# 007.net
KiCad netlist of a schematic drawn in EAGLE
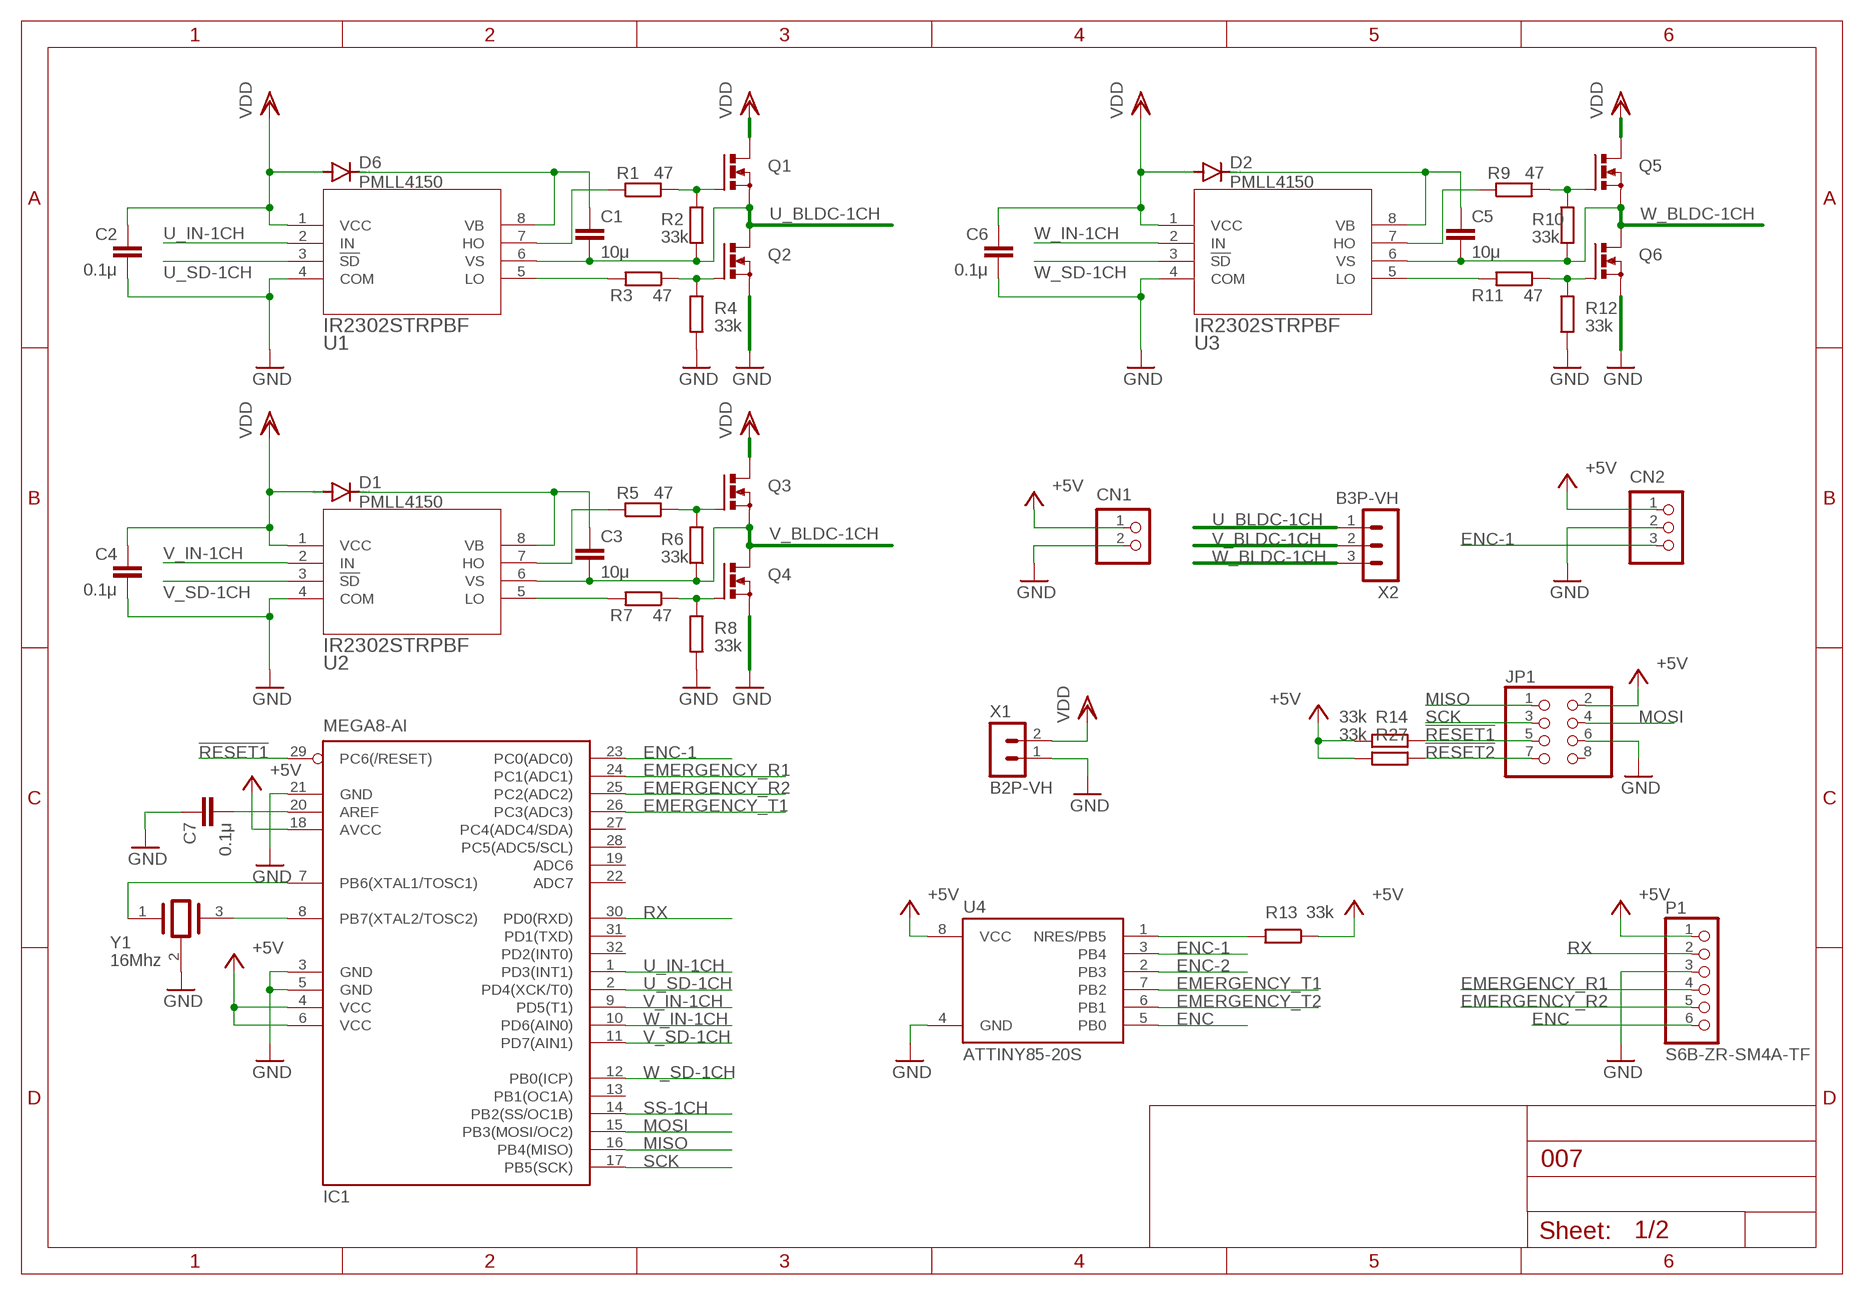
[diagram p0: schematic, sheet 1]
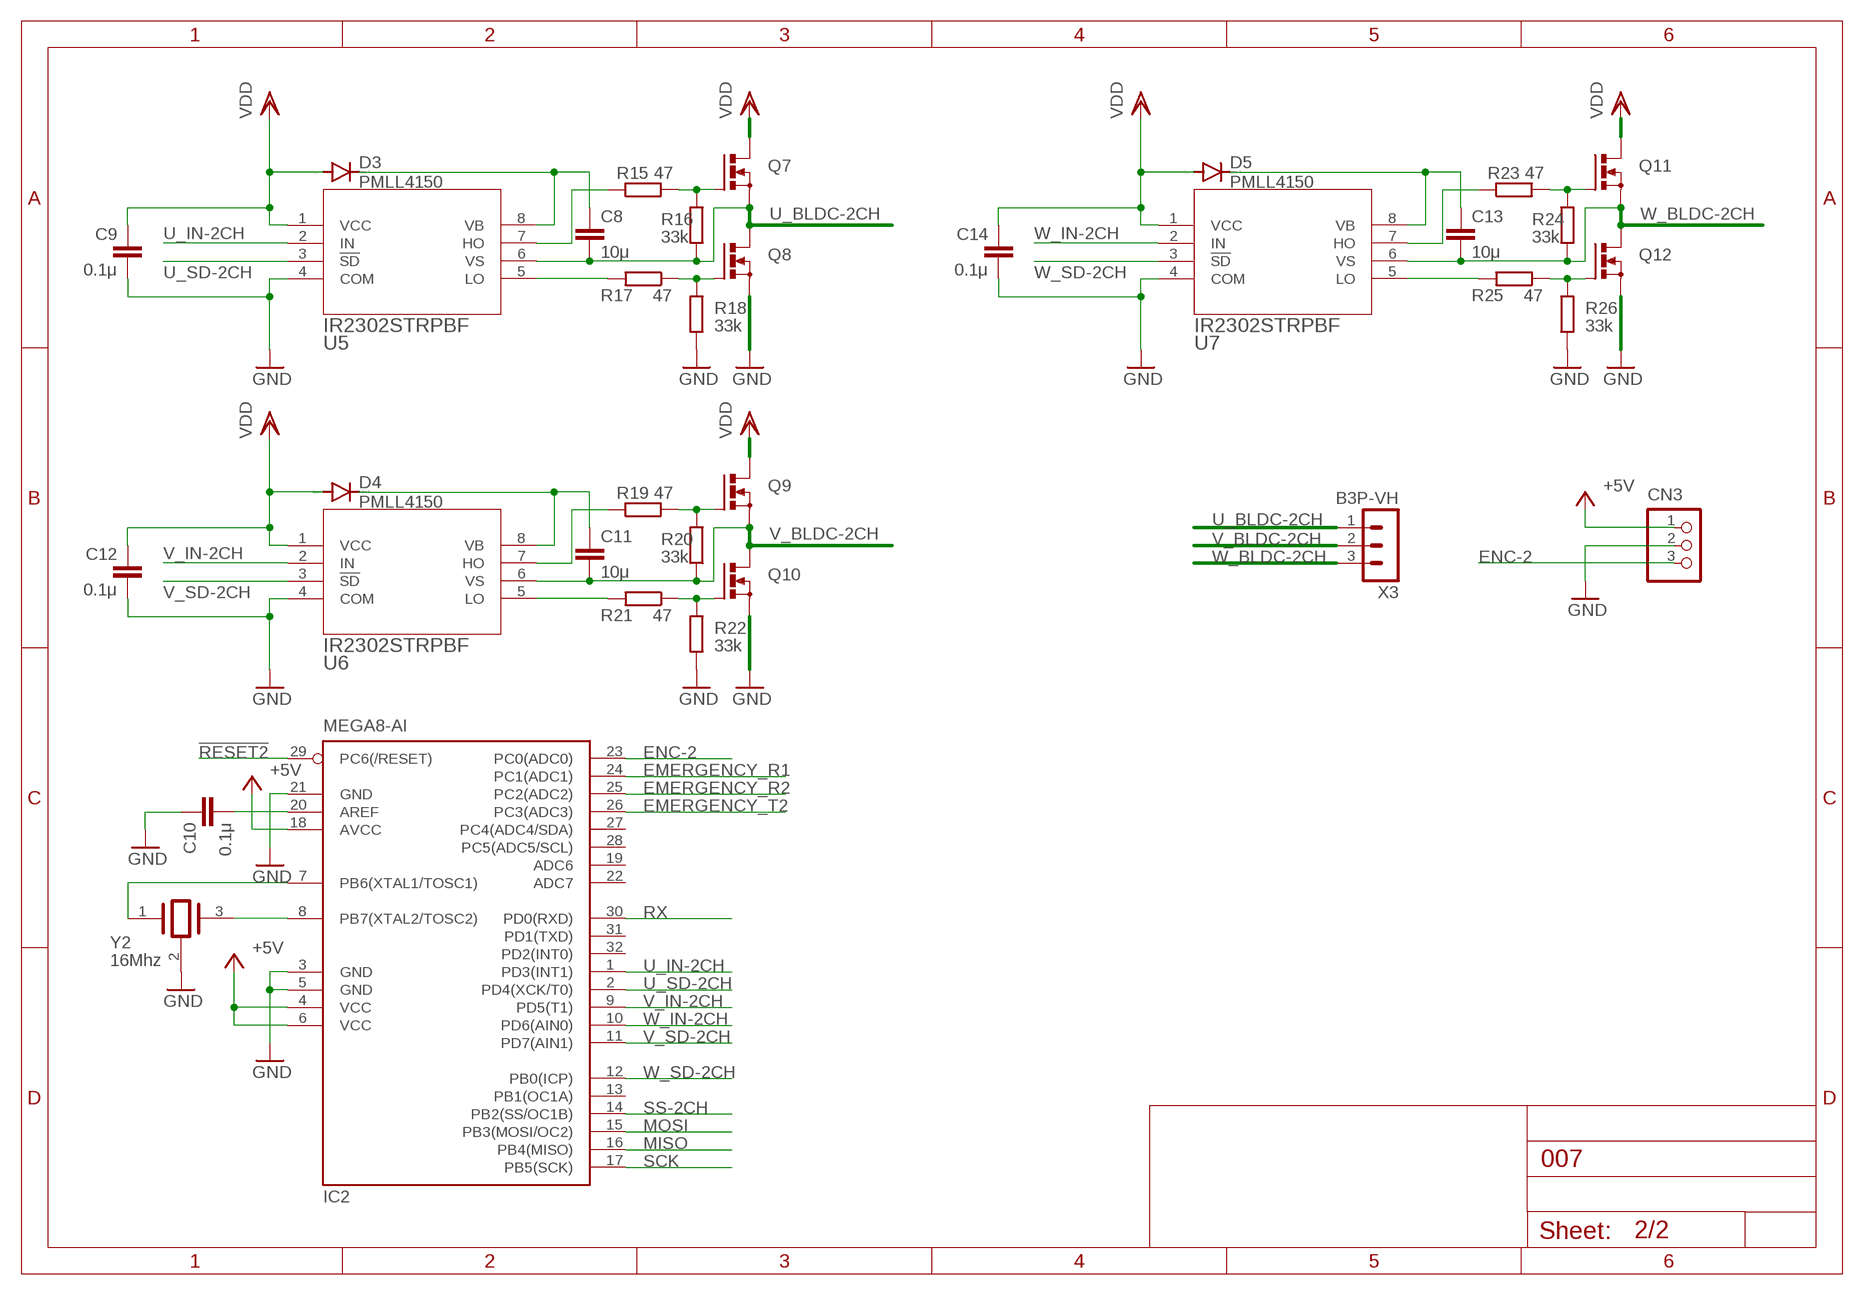
[diagram p1: schematic, sheet 2]

(export (version "E")
  (design (tool "Eeschema 10.0.6"))
  (components
    (comp (ref "C8")
      (value "10μ")
      (footprint "eagle-import:C1608")
      (libsource (lib "eagle-import") (part "C-EUC1608"))
    )
    (comp (ref "C9")
      (value "0.1μ")
      (footprint "eagle-import:C1608")
      (libsource (lib "eagle-import") (part "C-EUC1608"))
    )
    (comp (ref "C10")
      (value "0.1μ")
      (footprint "eagle-import:C1608")
      (libsource (lib "eagle-import") (part "C-EUC1608"))
    )
    (comp (ref "C11")
      (value "10μ")
      (footprint "eagle-import:C1608")
      (libsource (lib "eagle-import") (part "C-EUC1608"))
    )
    (comp (ref "C12")
      (value "0.1μ")
      (footprint "eagle-import:C1608")
      (libsource (lib "eagle-import") (part "C-EUC1608"))
    )
    (comp (ref "C13")
      (value "10μ")
      (footprint "eagle-import:C1608")
      (libsource (lib "eagle-import") (part "C-EUC1608"))
    )
    (comp (ref "C14")
      (value "0.1μ")
      (footprint "eagle-import:C1608")
      (libsource (lib "eagle-import") (part "C-EUC1608"))
    )
    (comp (ref "CN3")
      (value "B3B-PH-K-S")
      (footprint "eagle-import:B3B-PH-K-S")
      (libsource (lib "eagle-import") (part "B3B-PH-K-S"))
    )
    (comp (ref "D3")
      (value "PMLL4150")
      (footprint "eagle-import:SOD80C")
      (libsource (lib "eagle-import") (part "PMLL4150"))
    )
    (comp (ref "D4")
      (value "PMLL4150")
      (footprint "eagle-import:SOD80C")
      (libsource (lib "eagle-import") (part "PMLL4150"))
    )
    (comp (ref "D5")
      (value "PMLL4150")
      (footprint "eagle-import:SOD80C")
      (libsource (lib "eagle-import") (part "PMLL4150"))
    )
    (comp (ref "IC2")
      (value "MEGA8-AI")
      (footprint "eagle-import:TQFP32-08")
      (fields (field (name "MPN") "ATMEGA8-16AU"))
      (libsource (lib "eagle-import") (part "MEGA8-AI"))
    )
    (comp (ref "Q7")
      (value "N-MOSFET-SO8S")
      (footprint "eagle-import:SO-08")
      (libsource (lib "eagle-import") (part "N-MOSFET-SO8S"))
    )
    (comp (ref "Q8")
      (value "N-MOSFET-SO8S")
      (footprint "eagle-import:SO-08")
      (libsource (lib "eagle-import") (part "N-MOSFET-SO8S"))
    )
    (comp (ref "Q9")
      (value "N-MOSFET-SO8S")
      (footprint "eagle-import:SO-08")
      (libsource (lib "eagle-import") (part "N-MOSFET-SO8S"))
    )
    (comp (ref "Q10")
      (value "N-MOSFET-SO8S")
      (footprint "eagle-import:SO-08")
      (libsource (lib "eagle-import") (part "N-MOSFET-SO8S"))
    )
    (comp (ref "Q11")
      (value "N-MOSFET-SO8S")
      (footprint "eagle-import:SO-08")
      (libsource (lib "eagle-import") (part "N-MOSFET-SO8S"))
    )
    (comp (ref "Q12")
      (value "N-MOSFET-SO8S")
      (footprint "eagle-import:SO-08")
      (libsource (lib "eagle-import") (part "N-MOSFET-SO8S"))
    )
    (comp (ref "R15")
      (value "47")
      (footprint "eagle-import:R0603")
      (libsource (lib "eagle-import") (part "R-EU_R0603"))
    )
    (comp (ref "R16")
      (value "33k")
      (footprint "eagle-import:R0603")
      (libsource (lib "eagle-import") (part "R-EU_R0603"))
    )
    (comp (ref "R17")
      (value "47")
      (footprint "eagle-import:R0603")
      (libsource (lib "eagle-import") (part "R-EU_R0603"))
    )
    (comp (ref "R18")
      (value "33k")
      (footprint "eagle-import:R0603")
      (libsource (lib "eagle-import") (part "R-EU_R0603"))
    )
    (comp (ref "R19")
      (value "47")
      (footprint "eagle-import:R0603")
      (libsource (lib "eagle-import") (part "R-EU_R0603"))
    )
    (comp (ref "R20")
      (value "33k")
      (footprint "eagle-import:R0603")
      (libsource (lib "eagle-import") (part "R-EU_R0603"))
    )
    (comp (ref "R21")
      (value "47")
      (footprint "eagle-import:R0603")
      (libsource (lib "eagle-import") (part "R-EU_R0603"))
    )
    (comp (ref "R22")
      (value "33k")
      (footprint "eagle-import:R0603")
      (libsource (lib "eagle-import") (part "R-EU_R0603"))
    )
    (comp (ref "R23")
      (value "47")
      (footprint "eagle-import:R0603")
      (libsource (lib "eagle-import") (part "R-EU_R0603"))
    )
    (comp (ref "R24")
      (value "33k")
      (footprint "eagle-import:R0603")
      (libsource (lib "eagle-import") (part "R-EU_R0603"))
    )
    (comp (ref "R25")
      (value "47")
      (footprint "eagle-import:R0603")
      (libsource (lib "eagle-import") (part "R-EU_R0603"))
    )
    (comp (ref "R26")
      (value "33k")
      (footprint "eagle-import:R0603")
      (libsource (lib "eagle-import") (part "R-EU_R0603"))
    )
    (comp (ref "U5")
      (value "IR2302STRPBF")
      (footprint "eagle-import:PG-DSO-8-910_INF")
      (fields (field (name "COPYRIGHT") "Copyright (C) 2018 Accelerated Designs. All rights reserved"))
      (libsource (lib "eagle-import") (part "IR2302STRPBF"))
    )
    (comp (ref "U6")
      (value "IR2302STRPBF")
      (footprint "eagle-import:PG-DSO-8-910_INF")
      (fields (field (name "COPYRIGHT") "Copyright (C) 2018 Accelerated Designs. All rights reserved"))
      (libsource (lib "eagle-import") (part "IR2302STRPBF"))
    )
    (comp (ref "U7")
      (value "IR2302STRPBF")
      (footprint "eagle-import:PG-DSO-8-910_INF")
      (fields (field (name "COPYRIGHT") "Copyright (C) 2018 Accelerated Designs. All rights reserved"))
      (libsource (lib "eagle-import") (part "IR2302STRPBF"))
    )
    (comp (ref "X3")
      (value "B3P-VH")
      (footprint "eagle-import:B3P-VH")
      (libsource (lib "eagle-import") (part "B3P-VH"))
    )
    (comp (ref "Y2")
      (value "16Mhz")
      (footprint "eagle-import:MURATA_CSTNE16M0V53C000R0_0")
      (fields
        (field (name "DIGIKEY_PART_NUMBER") "490-17949-1-ND")
        (field (name "MF") "Murata")
        (field (name "MOUSER_PART_NUMBER") "81-CSTNE16M0V53C000R")
      )
      (libsource (lib "eagle-import") (part "MURATA_CSTNE16M0V53C000R0MURATA_CSTNE16M0V53C000R0_0_0"))
    )
    (comp (ref "C1")
      (value "10μ")
      (footprint "eagle-import:C1608")
      (libsource (lib "eagle-import") (part "C-EUC1608"))
    )
    (comp (ref "C2")
      (value "0.1μ")
      (footprint "eagle-import:C1608")
      (libsource (lib "eagle-import") (part "C-EUC1608"))
    )
    (comp (ref "C3")
      (value "10μ")
      (footprint "eagle-import:C1608")
      (libsource (lib "eagle-import") (part "C-EUC1608"))
    )
    (comp (ref "C4")
      (value "0.1μ")
      (footprint "eagle-import:C1608")
      (libsource (lib "eagle-import") (part "C-EUC1608"))
    )
    (comp (ref "C5")
      (value "10μ")
      (footprint "eagle-import:C1608")
      (libsource (lib "eagle-import") (part "C-EUC1608"))
    )
    (comp (ref "C6")
      (value "0.1μ")
      (footprint "eagle-import:C1608")
      (libsource (lib "eagle-import") (part "C-EUC1608"))
    )
    (comp (ref "C7")
      (value "0.1μ")
      (footprint "eagle-import:C1608")
      (libsource (lib "eagle-import") (part "C-EUC1608"))
    )
    (comp (ref "CN1")
      (value "B2B-PH-K-S")
      (footprint "eagle-import:B2B-PH-K-S")
      (libsource (lib "eagle-import") (part "B2B-PH-K-S"))
    )
    (comp (ref "CN2")
      (value "B3B-PH-K-S")
      (footprint "eagle-import:B3B-PH-K-S")
      (libsource (lib "eagle-import") (part "B3B-PH-K-S"))
    )
    (comp (ref "D1")
      (value "PMLL4150")
      (footprint "eagle-import:SOD80C")
      (libsource (lib "eagle-import") (part "PMLL4150"))
    )
    (comp (ref "D2")
      (value "PMLL4150")
      (footprint "eagle-import:SOD80C")
      (libsource (lib "eagle-import") (part "PMLL4150"))
    )
    (comp (ref "D6")
      (value "PMLL4150")
      (footprint "eagle-import:SOD80C")
      (libsource (lib "eagle-import") (part "PMLL4150"))
    )
    (comp (ref "IC1")
      (value "MEGA8-AI")
      (footprint "eagle-import:TQFP32-08")
      (fields (field (name "MPN") "ATMEGA8-16AU"))
      (libsource (lib "eagle-import") (part "MEGA8-AI"))
    )
    (comp (ref "JP1")
      (value "PINHD-2X4")
      (footprint "eagle-import:2X04")
      (libsource (lib "eagle-import") (part "PINHD-2X4"))
    )
    (comp (ref "P1")
      (value "S6B-ZR-SM4A-TF")
      (footprint "eagle-import:ZH-SM4-SIDE06")
      (libsource (lib "eagle-import") (part "S6B-ZR-SM4A-TF"))
    )
    (comp (ref "Q1")
      (value "N-MOSFET-SO8S")
      (footprint "eagle-import:SO-08")
      (libsource (lib "eagle-import") (part "N-MOSFET-SO8S"))
    )
    (comp (ref "Q2")
      (value "N-MOSFET-SO8S")
      (footprint "eagle-import:SO-08")
      (libsource (lib "eagle-import") (part "N-MOSFET-SO8S"))
    )
    (comp (ref "Q3")
      (value "N-MOSFET-SO8S")
      (footprint "eagle-import:SO-08")
      (libsource (lib "eagle-import") (part "N-MOSFET-SO8S"))
    )
    (comp (ref "Q4")
      (value "N-MOSFET-SO8S")
      (footprint "eagle-import:SO-08")
      (libsource (lib "eagle-import") (part "N-MOSFET-SO8S"))
    )
    (comp (ref "Q5")
      (value "N-MOSFET-SO8S")
      (footprint "eagle-import:SO-08")
      (libsource (lib "eagle-import") (part "N-MOSFET-SO8S"))
    )
    (comp (ref "Q6")
      (value "N-MOSFET-SO8S")
      (footprint "eagle-import:SO-08")
      (libsource (lib "eagle-import") (part "N-MOSFET-SO8S"))
    )
    (comp (ref "R1")
      (value "47")
      (footprint "eagle-import:R0603")
      (libsource (lib "eagle-import") (part "R-EU_R0603"))
    )
    (comp (ref "R2")
      (value "33k")
      (footprint "eagle-import:R0603")
      (libsource (lib "eagle-import") (part "R-EU_R0603"))
    )
    (comp (ref "R3")
      (value "47")
      (footprint "eagle-import:R0603")
      (libsource (lib "eagle-import") (part "R-EU_R0603"))
    )
    (comp (ref "R4")
      (value "33k")
      (footprint "eagle-import:R0603")
      (libsource (lib "eagle-import") (part "R-EU_R0603"))
    )
    (comp (ref "R5")
      (value "47")
      (footprint "eagle-import:R0603")
      (libsource (lib "eagle-import") (part "R-EU_R0603"))
    )
    (comp (ref "R6")
      (value "33k")
      (footprint "eagle-import:R0603")
      (libsource (lib "eagle-import") (part "R-EU_R0603"))
    )
    (comp (ref "R7")
      (value "47")
      (footprint "eagle-import:R0603")
      (libsource (lib "eagle-import") (part "R-EU_R0603"))
    )
    (comp (ref "R8")
      (value "33k")
      (footprint "eagle-import:R0603")
      (libsource (lib "eagle-import") (part "R-EU_R0603"))
    )
    (comp (ref "R9")
      (value "47")
      (footprint "eagle-import:R0603")
      (libsource (lib "eagle-import") (part "R-EU_R0603"))
    )
    (comp (ref "R10")
      (value "33k")
      (footprint "eagle-import:R0603")
      (libsource (lib "eagle-import") (part "R-EU_R0603"))
    )
    (comp (ref "R11")
      (value "47")
      (footprint "eagle-import:R0603")
      (libsource (lib "eagle-import") (part "R-EU_R0603"))
    )
    (comp (ref "R12")
      (value "33k")
      (footprint "eagle-import:R0603")
      (libsource (lib "eagle-import") (part "R-EU_R0603"))
    )
    (comp (ref "R13")
      (value "33k")
      (footprint "eagle-import:R0603")
      (libsource (lib "eagle-import") (part "R-EU_R0603"))
    )
    (comp (ref "R14")
      (value "33k")
      (footprint "eagle-import:R0603")
      (libsource (lib "eagle-import") (part "R-EU_R0603"))
    )
    (comp (ref "R27")
      (value "33k")
      (footprint "eagle-import:R0603")
      (libsource (lib "eagle-import") (part "R-EU_R0603"))
    )
    (comp (ref "U1")
      (value "IR2302STRPBF")
      (footprint "eagle-import:PG-DSO-8-910_INF")
      (fields (field (name "COPYRIGHT") "Copyright (C) 2018 Accelerated Designs. All rights reserved"))
      (libsource (lib "eagle-import") (part "IR2302STRPBF"))
    )
    (comp (ref "U2")
      (value "IR2302STRPBF")
      (footprint "eagle-import:PG-DSO-8-910_INF")
      (fields (field (name "COPYRIGHT") "Copyright (C) 2018 Accelerated Designs. All rights reserved"))
      (libsource (lib "eagle-import") (part "IR2302STRPBF"))
    )
    (comp (ref "U3")
      (value "IR2302STRPBF")
      (footprint "eagle-import:PG-DSO-8-910_INF")
      (fields (field (name "COPYRIGHT") "Copyright (C) 2018 Accelerated Designs. All rights reserved"))
      (libsource (lib "eagle-import") (part "IR2302STRPBF"))
    )
    (comp (ref "U4")
      (value "ATTINY85-20S")
      (footprint "eagle-import:SOIC8_EIAJ_208MIL")
      (libsource (lib "eagle-import") (part "ATTINY85S-20"))
    )
    (comp (ref "X1")
      (value "B2P-VH")
      (footprint "eagle-import:B2P-VH")
      (libsource (lib "eagle-import") (part "B2P-VH"))
    )
    (comp (ref "X2")
      (value "B3P-VH")
      (footprint "eagle-import:B3P-VH")
      (libsource (lib "eagle-import") (part "B3P-VH"))
    )
    (comp (ref "Y1")
      (value "16Mhz")
      (footprint "eagle-import:MURATA_CSTNE16M0V53C000R0_0")
      (fields
        (field (name "DIGIKEY_PART_NUMBER") "490-17949-1-ND")
        (field (name "MF") "Murata")
        (field (name "MOUSER_PART_NUMBER") "81-CSTNE16M0V53C000R")
      )
      (libsource (lib "eagle-import") (part "MURATA_CSTNE16M0V53C000R0MURATA_CSTNE16M0V53C000R0_0_0"))
    )
  )
  (nets
    (net (code "1") (name "+5V") (class "Default")
      (node (ref "CN1") (pin "1") (pinfunction "1_1") (pintype "passive"))
      (node (ref "CN2") (pin "1") (pinfunction "1_1") (pintype "passive"))
      (node (ref "CN3") (pin "1") (pinfunction "1_1") (pintype "passive"))
      (node (ref "IC1") (pin "18") (pinfunction "AVCC_18") (pintype "power_in"))
      (node (ref "IC1") (pin "4") (pinfunction "VCC_4") (pintype "power_in"))
      (node (ref "IC1") (pin "6") (pinfunction "VCC_6") (pintype "power_in"))
      (node (ref "IC2") (pin "18") (pinfunction "AVCC_18") (pintype "power_in"))
      (node (ref "IC2") (pin "4") (pinfunction "VCC_4") (pintype "power_in"))
      (node (ref "IC2") (pin "6") (pinfunction "VCC_6") (pintype "power_in"))
      (node (ref "JP1") (pin "2") (pinfunction "2_2") (pintype "passive"))
      (node (ref "P1") (pin "1") (pinfunction "1_1") (pintype "passive"))
      (node (ref "R13") (pin "1") (pinfunction "1_1") (pintype "passive"))
      (node (ref "R14") (pin "1") (pinfunction "1_1") (pintype "passive"))
      (node (ref "R27") (pin "1") (pinfunction "1_1") (pintype "passive"))
      (node (ref "U4") (pin "8") (pinfunction "VCC_8") (pintype "power_in"))
    )
    (net (code "2") (name "EMERGENCY_R1") (class "Default")
      (node (ref "IC1") (pin "24") (pinfunction "PC1(ADC1)_24") (pintype "bidirectional"))
      (node (ref "IC2") (pin "24") (pinfunction "PC1(ADC1)_24") (pintype "bidirectional"))
      (node (ref "P1") (pin "4") (pinfunction "4_4") (pintype "passive"))
    )
    (net (code "3") (name "EMERGENCY_R2") (class "Default")
      (node (ref "IC1") (pin "25") (pinfunction "PC2(ADC2)_25") (pintype "bidirectional"))
      (node (ref "IC2") (pin "25") (pinfunction "PC2(ADC2)_25") (pintype "bidirectional"))
      (node (ref "P1") (pin "5") (pinfunction "5_5") (pintype "passive"))
    )
    (net (code "4") (name "EMERGENCY_T1") (class "Default")
      (node (ref "IC1") (pin "26") (pinfunction "PC3(ADC3)_26") (pintype "bidirectional"))
      (node (ref "U4") (pin "7") (pinfunction "PB2_7") (pintype "bidirectional"))
    )
    (net (code "5") (name "EMERGENCY_T2") (class "Default")
      (node (ref "IC2") (pin "26") (pinfunction "PC3(ADC3)_26") (pintype "bidirectional"))
      (node (ref "U4") (pin "6") (pinfunction "PB1_6") (pintype "bidirectional"))
    )
    (net (code "6") (name "ENC") (class "Default")
      (node (ref "P1") (pin "6") (pinfunction "6_6") (pintype "passive"))
      (node (ref "U4") (pin "5") (pinfunction "PB0_5") (pintype "bidirectional"))
    )
    (net (code "7") (name "ENC-1") (class "Default")
      (node (ref "CN2") (pin "3") (pinfunction "3_3") (pintype "passive"))
      (node (ref "IC1") (pin "23") (pinfunction "PC0(ADC0)_23") (pintype "bidirectional"))
      (node (ref "U4") (pin "3") (pinfunction "PB4_3") (pintype "bidirectional"))
    )
    (net (code "8") (name "ENC-2") (class "Default")
      (node (ref "CN3") (pin "3") (pinfunction "3_3") (pintype "passive"))
      (node (ref "IC2") (pin "23") (pinfunction "PC0(ADC0)_23") (pintype "bidirectional"))
      (node (ref "U4") (pin "2") (pinfunction "PB3_2") (pintype "bidirectional"))
    )
    (net (code "9") (name "GND") (class "Default")
      (node (ref "C10") (pin "2") (pinfunction "2_2") (pintype "passive"))
      (node (ref "C12") (pin "1") (pinfunction "1_1") (pintype "passive"))
      (node (ref "C14") (pin "1") (pinfunction "1_1") (pintype "passive"))
      (node (ref "C2") (pin "1") (pinfunction "1_1") (pintype "passive"))
      (node (ref "C4") (pin "1") (pinfunction "1_1") (pintype "passive"))
      (node (ref "C6") (pin "1") (pinfunction "1_1") (pintype "passive"))
      (node (ref "C7") (pin "2") (pinfunction "2_2") (pintype "passive"))
      (node (ref "C9") (pin "1") (pinfunction "1_1") (pintype "passive"))
      (node (ref "CN1") (pin "2") (pinfunction "2_2") (pintype "passive"))
      (node (ref "CN2") (pin "2") (pinfunction "2_2") (pintype "passive"))
      (node (ref "CN3") (pin "2") (pinfunction "2_2") (pintype "passive"))
      (node (ref "IC1") (pin "21") (pinfunction "GND_21") (pintype "power_in"))
      (node (ref "IC1") (pin "3") (pinfunction "GND_3") (pintype "power_in"))
      (node (ref "IC1") (pin "5") (pinfunction "GND_5") (pintype "power_in"))
      (node (ref "IC2") (pin "21") (pinfunction "GND_21") (pintype "power_in"))
      (node (ref "IC2") (pin "3") (pinfunction "GND_3") (pintype "power_in"))
      (node (ref "IC2") (pin "5") (pinfunction "GND_5") (pintype "power_in"))
      (node (ref "JP1") (pin "6") (pinfunction "6_6") (pintype "passive"))
      (node (ref "P1") (pin "3") (pinfunction "3_3") (pintype "passive"))
      (node (ref "Q10") (pin "1") (pinfunction "S_1") (pintype "passive"))
      (node (ref "Q10") (pin "2") (pinfunction "S_2") (pintype "passive"))
      (node (ref "Q10") (pin "3") (pinfunction "S_3") (pintype "passive"))
      (node (ref "Q12") (pin "1") (pinfunction "S_1") (pintype "passive"))
      (node (ref "Q12") (pin "2") (pinfunction "S_2") (pintype "passive"))
      (node (ref "Q12") (pin "3") (pinfunction "S_3") (pintype "passive"))
      (node (ref "Q2") (pin "1") (pinfunction "S_1") (pintype "passive"))
      (node (ref "Q2") (pin "2") (pinfunction "S_2") (pintype "passive"))
      (node (ref "Q2") (pin "3") (pinfunction "S_3") (pintype "passive"))
      (node (ref "Q4") (pin "1") (pinfunction "S_1") (pintype "passive"))
      (node (ref "Q4") (pin "2") (pinfunction "S_2") (pintype "passive"))
      (node (ref "Q4") (pin "3") (pinfunction "S_3") (pintype "passive"))
      (node (ref "Q6") (pin "1") (pinfunction "S_1") (pintype "passive"))
      (node (ref "Q6") (pin "2") (pinfunction "S_2") (pintype "passive"))
      (node (ref "Q6") (pin "3") (pinfunction "S_3") (pintype "passive"))
      (node (ref "Q8") (pin "1") (pinfunction "S_1") (pintype "passive"))
      (node (ref "Q8") (pin "2") (pinfunction "S_2") (pintype "passive"))
      (node (ref "Q8") (pin "3") (pinfunction "S_3") (pintype "passive"))
      (node (ref "R12") (pin "1") (pinfunction "1_1") (pintype "passive"))
      (node (ref "R18") (pin "1") (pinfunction "1_1") (pintype "passive"))
      (node (ref "R22") (pin "1") (pinfunction "1_1") (pintype "passive"))
      (node (ref "R26") (pin "1") (pinfunction "1_1") (pintype "passive"))
      (node (ref "R4") (pin "1") (pinfunction "1_1") (pintype "passive"))
      (node (ref "R8") (pin "1") (pinfunction "1_1") (pintype "passive"))
      (node (ref "U1") (pin "4") (pinfunction "COM_4") (pintype "passive"))
      (node (ref "U2") (pin "4") (pinfunction "COM_4") (pintype "passive"))
      (node (ref "U3") (pin "4") (pinfunction "COM_4") (pintype "passive"))
      (node (ref "U4") (pin "4") (pinfunction "GND_4") (pintype "power_in"))
      (node (ref "U5") (pin "4") (pinfunction "COM_4") (pintype "passive"))
      (node (ref "U6") (pin "4") (pinfunction "COM_4") (pintype "passive"))
      (node (ref "U7") (pin "4") (pinfunction "COM_4") (pintype "passive"))
      (node (ref "X1") (pin "1") (pinfunction "1_1") (pintype "passive"))
      (node (ref "Y1") (pin "2") (pinfunction "GND_2") (pintype "power_in"))
      (node (ref "Y2") (pin "2") (pinfunction "GND_2") (pintype "power_in"))
    )
    (net (code "10") (name "MISO") (class "Default")
      (node (ref "IC1") (pin "16") (pinfunction "PB4(MISO)_16") (pintype "bidirectional"))
      (node (ref "IC2") (pin "16") (pinfunction "PB4(MISO)_16") (pintype "bidirectional"))
      (node (ref "JP1") (pin "1") (pinfunction "1_1") (pintype "passive"))
    )
    (net (code "11") (name "MOSI") (class "Default")
      (node (ref "IC1") (pin "15") (pinfunction "PB3(MOSI/OC2)_15") (pintype "bidirectional"))
      (node (ref "IC2") (pin "15") (pinfunction "PB3(MOSI/OC2)_15") (pintype "bidirectional"))
      (node (ref "JP1") (pin "4") (pinfunction "4_4") (pintype "passive"))
    )
    (net (code "12") (name "Net-(IC1-AREF)") (class "Default")
      (node (ref "C7") (pin "1") (pinfunction "1_1") (pintype "passive"))
      (node (ref "IC1") (pin "20") (pinfunction "AREF_20") (pintype "passive"))
    )
    (net (code "13") (name "Net-(IC1-PB6(XTAL1{slash}TOSC1))") (class "Default")
      (node (ref "IC1") (pin "7") (pinfunction "PB6(XTAL1/TOSC1)_7") (pintype "bidirectional"))
      (node (ref "Y1") (pin "1") (pinfunction "INPUT_1") (pintype "input"))
    )
    (net (code "14") (name "Net-(IC1-PB7(XTAL2{slash}TOSC2))") (class "Default")
      (node (ref "IC1") (pin "8") (pinfunction "PB7(XTAL2/TOSC2)_8") (pintype "bidirectional"))
      (node (ref "Y1") (pin "3") (pinfunction "OUTPUT_3") (pintype "output"))
    )
    (net (code "15") (name "Net-(IC2-AREF)") (class "Default")
      (node (ref "C10") (pin "1") (pinfunction "1_1") (pintype "passive"))
      (node (ref "IC2") (pin "20") (pinfunction "AREF_20") (pintype "passive"))
    )
    (net (code "16") (name "Net-(IC2-PB6(XTAL1{slash}TOSC1))") (class "Default")
      (node (ref "IC2") (pin "7") (pinfunction "PB6(XTAL1/TOSC1)_7") (pintype "bidirectional"))
      (node (ref "Y2") (pin "1") (pinfunction "INPUT_1") (pintype "input"))
    )
    (net (code "17") (name "Net-(IC2-PB7(XTAL2{slash}TOSC2))") (class "Default")
      (node (ref "IC2") (pin "8") (pinfunction "PB7(XTAL2/TOSC2)_8") (pintype "bidirectional"))
      (node (ref "Y2") (pin "3") (pinfunction "OUTPUT_3") (pintype "output"))
    )
    (net (code "18") (name "Net-(Q1-G)") (class "Default")
      (node (ref "Q1") (pin "4") (pinfunction "G_4") (pintype "passive"))
      (node (ref "R1") (pin "2") (pinfunction "2_2") (pintype "passive"))
      (node (ref "R2") (pin "2") (pinfunction "2_2") (pintype "passive"))
    )
    (net (code "19") (name "Net-(Q2-G)") (class "Default")
      (node (ref "Q2") (pin "4") (pinfunction "G_4") (pintype "passive"))
      (node (ref "R3") (pin "1") (pinfunction "1_1") (pintype "passive"))
      (node (ref "R4") (pin "2") (pinfunction "2_2") (pintype "passive"))
    )
    (net (code "20") (name "Net-(Q3-G)") (class "Default")
      (node (ref "Q3") (pin "4") (pinfunction "G_4") (pintype "passive"))
      (node (ref "R5") (pin "2") (pinfunction "2_2") (pintype "passive"))
      (node (ref "R6") (pin "2") (pinfunction "2_2") (pintype "passive"))
    )
    (net (code "21") (name "Net-(Q4-G)") (class "Default")
      (node (ref "Q4") (pin "4") (pinfunction "G_4") (pintype "passive"))
      (node (ref "R7") (pin "1") (pinfunction "1_1") (pintype "passive"))
      (node (ref "R8") (pin "2") (pinfunction "2_2") (pintype "passive"))
    )
    (net (code "22") (name "Net-(Q5-G)") (class "Default")
      (node (ref "Q5") (pin "4") (pinfunction "G_4") (pintype "passive"))
      (node (ref "R10") (pin "2") (pinfunction "2_2") (pintype "passive"))
      (node (ref "R9") (pin "2") (pinfunction "2_2") (pintype "passive"))
    )
    (net (code "23") (name "Net-(Q6-G)") (class "Default")
      (node (ref "Q6") (pin "4") (pinfunction "G_4") (pintype "passive"))
      (node (ref "R11") (pin "1") (pinfunction "1_1") (pintype "passive"))
      (node (ref "R12") (pin "2") (pinfunction "2_2") (pintype "passive"))
    )
    (net (code "24") (name "Net-(Q7-G)") (class "Default")
      (node (ref "Q7") (pin "4") (pinfunction "G_4") (pintype "passive"))
      (node (ref "R15") (pin "2") (pinfunction "2_2") (pintype "passive"))
      (node (ref "R16") (pin "2") (pinfunction "2_2") (pintype "passive"))
    )
    (net (code "25") (name "Net-(Q8-G)") (class "Default")
      (node (ref "Q8") (pin "4") (pinfunction "G_4") (pintype "passive"))
      (node (ref "R17") (pin "1") (pinfunction "1_1") (pintype "passive"))
      (node (ref "R18") (pin "2") (pinfunction "2_2") (pintype "passive"))
    )
    (net (code "26") (name "Net-(Q9-G)") (class "Default")
      (node (ref "Q9") (pin "4") (pinfunction "G_4") (pintype "passive"))
      (node (ref "R19") (pin "2") (pinfunction "2_2") (pintype "passive"))
      (node (ref "R20") (pin "2") (pinfunction "2_2") (pintype "passive"))
    )
    (net (code "27") (name "Net-(Q10-G)") (class "Default")
      (node (ref "Q10") (pin "4") (pinfunction "G_4") (pintype "passive"))
      (node (ref "R21") (pin "1") (pinfunction "1_1") (pintype "passive"))
      (node (ref "R22") (pin "2") (pinfunction "2_2") (pintype "passive"))
    )
    (net (code "28") (name "Net-(Q11-G)") (class "Default")
      (node (ref "Q11") (pin "4") (pinfunction "G_4") (pintype "passive"))
      (node (ref "R23") (pin "2") (pinfunction "2_2") (pintype "passive"))
      (node (ref "R24") (pin "2") (pinfunction "2_2") (pintype "passive"))
    )
    (net (code "29") (name "Net-(Q12-G)") (class "Default")
      (node (ref "Q12") (pin "4") (pinfunction "G_4") (pintype "passive"))
      (node (ref "R25") (pin "1") (pinfunction "1_1") (pintype "passive"))
      (node (ref "R26") (pin "2") (pinfunction "2_2") (pintype "passive"))
    )
    (net (code "30") (name "Net-(U1-HO)") (class "Default")
      (node (ref "R1") (pin "1") (pinfunction "1_1") (pintype "passive"))
      (node (ref "U1") (pin "7") (pinfunction "HO_7") (pintype "output"))
    )
    (net (code "31") (name "Net-(U1-LO)") (class "Default")
      (node (ref "R3") (pin "2") (pinfunction "2_2") (pintype "passive"))
      (node (ref "U1") (pin "5") (pinfunction "LO_5") (pintype "output"))
    )
    (net (code "32") (name "Net-(U1-VB)") (class "Default")
      (node (ref "C1") (pin "1") (pinfunction "1_1") (pintype "passive"))
      (node (ref "D6") (pin "C") (pinfunction "C_C") (pintype "passive"))
      (node (ref "U1") (pin "8") (pinfunction "VB_8") (pintype "power_in"))
    )
    (net (code "33") (name "Net-(U2-HO)") (class "Default")
      (node (ref "R5") (pin "1") (pinfunction "1_1") (pintype "passive"))
      (node (ref "U2") (pin "7") (pinfunction "HO_7") (pintype "output"))
    )
    (net (code "34") (name "Net-(U2-LO)") (class "Default")
      (node (ref "R7") (pin "2") (pinfunction "2_2") (pintype "passive"))
      (node (ref "U2") (pin "5") (pinfunction "LO_5") (pintype "output"))
    )
    (net (code "35") (name "Net-(U2-VB)") (class "Default")
      (node (ref "C3") (pin "1") (pinfunction "1_1") (pintype "passive"))
      (node (ref "D1") (pin "C") (pinfunction "C_C") (pintype "passive"))
      (node (ref "U2") (pin "8") (pinfunction "VB_8") (pintype "power_in"))
    )
    (net (code "36") (name "Net-(U3-HO)") (class "Default")
      (node (ref "R9") (pin "1") (pinfunction "1_1") (pintype "passive"))
      (node (ref "U3") (pin "7") (pinfunction "HO_7") (pintype "output"))
    )
    (net (code "37") (name "Net-(U3-LO)") (class "Default")
      (node (ref "R11") (pin "2") (pinfunction "2_2") (pintype "passive"))
      (node (ref "U3") (pin "5") (pinfunction "LO_5") (pintype "output"))
    )
    (net (code "38") (name "Net-(U3-VB)") (class "Default")
      (node (ref "C5") (pin "1") (pinfunction "1_1") (pintype "passive"))
      (node (ref "D2") (pin "C") (pinfunction "C_C") (pintype "passive"))
      (node (ref "U3") (pin "8") (pinfunction "VB_8") (pintype "power_in"))
    )
    (net (code "39") (name "Net-(U4-NRES{slash}PB5)") (class "Default")
      (node (ref "R13") (pin "2") (pinfunction "2_2") (pintype "passive"))
      (node (ref "U4") (pin "1") (pinfunction "NRES/PB5_1") (pintype "bidirectional"))
    )
    (net (code "40") (name "Net-(U5-HO)") (class "Default")
      (node (ref "R15") (pin "1") (pinfunction "1_1") (pintype "passive"))
      (node (ref "U5") (pin "7") (pinfunction "HO_7") (pintype "output"))
    )
    (net (code "41") (name "Net-(U5-LO)") (class "Default")
      (node (ref "R17") (pin "2") (pinfunction "2_2") (pintype "passive"))
      (node (ref "U5") (pin "5") (pinfunction "LO_5") (pintype "output"))
    )
    (net (code "42") (name "Net-(U5-VB)") (class "Default")
      (node (ref "C8") (pin "1") (pinfunction "1_1") (pintype "passive"))
      (node (ref "D3") (pin "C") (pinfunction "C_C") (pintype "passive"))
      (node (ref "U5") (pin "8") (pinfunction "VB_8") (pintype "power_in"))
    )
    (net (code "43") (name "Net-(U6-HO)") (class "Default")
      (node (ref "R19") (pin "1") (pinfunction "1_1") (pintype "passive"))
      (node (ref "U6") (pin "7") (pinfunction "HO_7") (pintype "output"))
    )
    (net (code "44") (name "Net-(U6-LO)") (class "Default")
      (node (ref "R21") (pin "2") (pinfunction "2_2") (pintype "passive"))
      (node (ref "U6") (pin "5") (pinfunction "LO_5") (pintype "output"))
    )
    (net (code "45") (name "Net-(U6-VB)") (class "Default")
      (node (ref "C11") (pin "1") (pinfunction "1_1") (pintype "passive"))
      (node (ref "D4") (pin "C") (pinfunction "C_C") (pintype "passive"))
      (node (ref "U6") (pin "8") (pinfunction "VB_8") (pintype "power_in"))
    )
    (net (code "46") (name "Net-(U7-HO)") (class "Default")
      (node (ref "R23") (pin "1") (pinfunction "1_1") (pintype "passive"))
      (node (ref "U7") (pin "7") (pinfunction "HO_7") (pintype "output"))
    )
    (net (code "47") (name "Net-(U7-LO)") (class "Default")
      (node (ref "R25") (pin "2") (pinfunction "2_2") (pintype "passive"))
      (node (ref "U7") (pin "5") (pinfunction "LO_5") (pintype "output"))
    )
    (net (code "48") (name "Net-(U7-VB)") (class "Default")
      (node (ref "C13") (pin "1") (pinfunction "1_1") (pintype "passive"))
      (node (ref "D5") (pin "C") (pinfunction "C_C") (pintype "passive"))
      (node (ref "U7") (pin "8") (pinfunction "VB_8") (pintype "power_in"))
    )
    (net (code "49") (name "RX") (class "Default")
      (node (ref "IC1") (pin "30") (pinfunction "PD0(RXD)_30") (pintype "bidirectional"))
      (node (ref "IC2") (pin "30") (pinfunction "PD0(RXD)_30") (pintype "bidirectional"))
      (node (ref "P1") (pin "2") (pinfunction "2_2") (pintype "passive"))
    )
    (net (code "50") (name "SCK") (class "Default")
      (node (ref "IC1") (pin "17") (pinfunction "PB5(SCK)_17") (pintype "bidirectional"))
      (node (ref "IC2") (pin "17") (pinfunction "PB5(SCK)_17") (pintype "bidirectional"))
      (node (ref "JP1") (pin "3") (pinfunction "3_3") (pintype "passive"))
    )
    (net (code "51") (name "SS-1CH") (class "Default")
      (node (ref "IC1") (pin "14") (pinfunction "PB2(SS/OC1B)_14") (pintype "bidirectional"))
    )
    (net (code "52") (name "SS-2CH") (class "Default")
      (node (ref "IC2") (pin "14") (pinfunction "PB2(SS/OC1B)_14") (pintype "bidirectional"))
    )
    (net (code "53") (name "U_BLDC-1CH") (class "Default")
      (node (ref "C1") (pin "2") (pinfunction "2_2") (pintype "passive"))
      (node (ref "Q1") (pin "1") (pinfunction "S_1") (pintype "passive"))
      (node (ref "Q1") (pin "2") (pinfunction "S_2") (pintype "passive"))
      (node (ref "Q1") (pin "3") (pinfunction "S_3") (pintype "passive"))
      (node (ref "Q2") (pin "5") (pinfunction "D_5") (pintype "passive"))
      (node (ref "Q2") (pin "6") (pinfunction "D_6") (pintype "passive"))
      (node (ref "Q2") (pin "7") (pinfunction "D_7") (pintype "passive"))
      (node (ref "Q2") (pin "8") (pinfunction "D_8") (pintype "passive"))
      (node (ref "R2") (pin "1") (pinfunction "1_1") (pintype "passive"))
      (node (ref "U1") (pin "6") (pinfunction "VS_6") (pintype "power_in"))
      (node (ref "X2") (pin "1") (pinfunction "1_1") (pintype "passive"))
    )
    (net (code "54") (name "U_BLDC-2CH") (class "Default")
      (node (ref "C8") (pin "2") (pinfunction "2_2") (pintype "passive"))
      (node (ref "Q7") (pin "1") (pinfunction "S_1") (pintype "passive"))
      (node (ref "Q7") (pin "2") (pinfunction "S_2") (pintype "passive"))
      (node (ref "Q7") (pin "3") (pinfunction "S_3") (pintype "passive"))
      (node (ref "Q8") (pin "5") (pinfunction "D_5") (pintype "passive"))
      (node (ref "Q8") (pin "6") (pinfunction "D_6") (pintype "passive"))
      (node (ref "Q8") (pin "7") (pinfunction "D_7") (pintype "passive"))
      (node (ref "Q8") (pin "8") (pinfunction "D_8") (pintype "passive"))
      (node (ref "R16") (pin "1") (pinfunction "1_1") (pintype "passive"))
      (node (ref "U5") (pin "6") (pinfunction "VS_6") (pintype "power_in"))
      (node (ref "X3") (pin "1") (pinfunction "1_1") (pintype "passive"))
    )
    (net (code "55") (name "U_IN-1CH") (class "Default")
      (node (ref "IC1") (pin "1") (pinfunction "PD3(INT1)_1") (pintype "bidirectional"))
      (node (ref "U1") (pin "2") (pinfunction "IN_2") (pintype "input"))
    )
    (net (code "56") (name "U_IN-2CH") (class "Default")
      (node (ref "IC2") (pin "1") (pinfunction "PD3(INT1)_1") (pintype "bidirectional"))
      (node (ref "U5") (pin "2") (pinfunction "IN_2") (pintype "input"))
    )
    (net (code "57") (name "U_SD-1CH") (class "Default")
      (node (ref "IC1") (pin "2") (pinfunction "PD4(XCK/T0)_2") (pintype "bidirectional"))
      (node (ref "U1") (pin "3") (pinfunction "~{SD}_3") (pintype "input"))
    )
    (net (code "58") (name "U_SD-2CH") (class "Default")
      (node (ref "IC2") (pin "2") (pinfunction "PD4(XCK/T0)_2") (pintype "bidirectional"))
      (node (ref "U5") (pin "3") (pinfunction "~{SD}_3") (pintype "input"))
    )
    (net (code "59") (name "VDD") (class "Default")
      (node (ref "C12") (pin "2") (pinfunction "2_2") (pintype "passive"))
      (node (ref "C14") (pin "2") (pinfunction "2_2") (pintype "passive"))
      (node (ref "C2") (pin "2") (pinfunction "2_2") (pintype "passive"))
      (node (ref "C4") (pin "2") (pinfunction "2_2") (pintype "passive"))
      (node (ref "C6") (pin "2") (pinfunction "2_2") (pintype "passive"))
      (node (ref "C9") (pin "2") (pinfunction "2_2") (pintype "passive"))
      (node (ref "D1") (pin "A") (pinfunction "A_A") (pintype "passive"))
      (node (ref "D2") (pin "A") (pinfunction "A_A") (pintype "passive"))
      (node (ref "D3") (pin "A") (pinfunction "A_A") (pintype "passive"))
      (node (ref "D4") (pin "A") (pinfunction "A_A") (pintype "passive"))
      (node (ref "D5") (pin "A") (pinfunction "A_A") (pintype "passive"))
      (node (ref "D6") (pin "A") (pinfunction "A_A") (pintype "passive"))
      (node (ref "Q1") (pin "5") (pinfunction "D_5") (pintype "passive"))
      (node (ref "Q1") (pin "6") (pinfunction "D_6") (pintype "passive"))
      (node (ref "Q1") (pin "7") (pinfunction "D_7") (pintype "passive"))
      (node (ref "Q1") (pin "8") (pinfunction "D_8") (pintype "passive"))
      (node (ref "Q11") (pin "5") (pinfunction "D_5") (pintype "passive"))
      (node (ref "Q11") (pin "6") (pinfunction "D_6") (pintype "passive"))
      (node (ref "Q11") (pin "7") (pinfunction "D_7") (pintype "passive"))
      (node (ref "Q11") (pin "8") (pinfunction "D_8") (pintype "passive"))
      (node (ref "Q3") (pin "5") (pinfunction "D_5") (pintype "passive"))
      (node (ref "Q3") (pin "6") (pinfunction "D_6") (pintype "passive"))
      (node (ref "Q3") (pin "7") (pinfunction "D_7") (pintype "passive"))
      (node (ref "Q3") (pin "8") (pinfunction "D_8") (pintype "passive"))
      (node (ref "Q5") (pin "5") (pinfunction "D_5") (pintype "passive"))
      (node (ref "Q5") (pin "6") (pinfunction "D_6") (pintype "passive"))
      (node (ref "Q5") (pin "7") (pinfunction "D_7") (pintype "passive"))
      (node (ref "Q5") (pin "8") (pinfunction "D_8") (pintype "passive"))
      (node (ref "Q7") (pin "5") (pinfunction "D_5") (pintype "passive"))
      (node (ref "Q7") (pin "6") (pinfunction "D_6") (pintype "passive"))
      (node (ref "Q7") (pin "7") (pinfunction "D_7") (pintype "passive"))
      (node (ref "Q7") (pin "8") (pinfunction "D_8") (pintype "passive"))
      (node (ref "Q9") (pin "5") (pinfunction "D_5") (pintype "passive"))
      (node (ref "Q9") (pin "6") (pinfunction "D_6") (pintype "passive"))
      (node (ref "Q9") (pin "7") (pinfunction "D_7") (pintype "passive"))
      (node (ref "Q9") (pin "8") (pinfunction "D_8") (pintype "passive"))
      (node (ref "U1") (pin "1") (pinfunction "VCC_1") (pintype "power_in"))
      (node (ref "U2") (pin "1") (pinfunction "VCC_1") (pintype "power_in"))
      (node (ref "U3") (pin "1") (pinfunction "VCC_1") (pintype "power_in"))
      (node (ref "U5") (pin "1") (pinfunction "VCC_1") (pintype "power_in"))
      (node (ref "U6") (pin "1") (pinfunction "VCC_1") (pintype "power_in"))
      (node (ref "U7") (pin "1") (pinfunction "VCC_1") (pintype "power_in"))
      (node (ref "X1") (pin "2") (pinfunction "2_2") (pintype "passive"))
    )
    (net (code "60") (name "V_BLDC-1CH") (class "Default")
      (node (ref "C3") (pin "2") (pinfunction "2_2") (pintype "passive"))
      (node (ref "Q3") (pin "1") (pinfunction "S_1") (pintype "passive"))
      (node (ref "Q3") (pin "2") (pinfunction "S_2") (pintype "passive"))
      (node (ref "Q3") (pin "3") (pinfunction "S_3") (pintype "passive"))
      (node (ref "Q4") (pin "5") (pinfunction "D_5") (pintype "passive"))
      (node (ref "Q4") (pin "6") (pinfunction "D_6") (pintype "passive"))
      (node (ref "Q4") (pin "7") (pinfunction "D_7") (pintype "passive"))
      (node (ref "Q4") (pin "8") (pinfunction "D_8") (pintype "passive"))
      (node (ref "R6") (pin "1") (pinfunction "1_1") (pintype "passive"))
      (node (ref "U2") (pin "6") (pinfunction "VS_6") (pintype "power_in"))
      (node (ref "X2") (pin "2") (pinfunction "2_2") (pintype "passive"))
    )
    (net (code "61") (name "V_BLDC-2CH") (class "Default")
      (node (ref "C11") (pin "2") (pinfunction "2_2") (pintype "passive"))
      (node (ref "Q10") (pin "5") (pinfunction "D_5") (pintype "passive"))
      (node (ref "Q10") (pin "6") (pinfunction "D_6") (pintype "passive"))
      (node (ref "Q10") (pin "7") (pinfunction "D_7") (pintype "passive"))
      (node (ref "Q10") (pin "8") (pinfunction "D_8") (pintype "passive"))
      (node (ref "Q9") (pin "1") (pinfunction "S_1") (pintype "passive"))
      (node (ref "Q9") (pin "2") (pinfunction "S_2") (pintype "passive"))
      (node (ref "Q9") (pin "3") (pinfunction "S_3") (pintype "passive"))
      (node (ref "R20") (pin "1") (pinfunction "1_1") (pintype "passive"))
      (node (ref "U6") (pin "6") (pinfunction "VS_6") (pintype "power_in"))
      (node (ref "X3") (pin "2") (pinfunction "2_2") (pintype "passive"))
    )
    (net (code "62") (name "V_IN-1CH") (class "Default")
      (node (ref "IC1") (pin "9") (pinfunction "PD5(T1)_9") (pintype "bidirectional"))
      (node (ref "U2") (pin "2") (pinfunction "IN_2") (pintype "input"))
    )
    (net (code "63") (name "V_IN-2CH") (class "Default")
      (node (ref "IC2") (pin "9") (pinfunction "PD5(T1)_9") (pintype "bidirectional"))
      (node (ref "U6") (pin "2") (pinfunction "IN_2") (pintype "input"))
    )
    (net (code "64") (name "V_SD-1CH") (class "Default")
      (node (ref "IC1") (pin "11") (pinfunction "PD7(AIN1)_11") (pintype "bidirectional"))
      (node (ref "U2") (pin "3") (pinfunction "~{SD}_3") (pintype "input"))
    )
    (net (code "65") (name "V_SD-2CH") (class "Default")
      (node (ref "IC2") (pin "11") (pinfunction "PD7(AIN1)_11") (pintype "bidirectional"))
      (node (ref "U6") (pin "3") (pinfunction "~{SD}_3") (pintype "input"))
    )
    (net (code "66") (name "W_BLDC-1CH") (class "Default")
      (node (ref "C5") (pin "2") (pinfunction "2_2") (pintype "passive"))
      (node (ref "Q5") (pin "1") (pinfunction "S_1") (pintype "passive"))
      (node (ref "Q5") (pin "2") (pinfunction "S_2") (pintype "passive"))
      (node (ref "Q5") (pin "3") (pinfunction "S_3") (pintype "passive"))
      (node (ref "Q6") (pin "5") (pinfunction "D_5") (pintype "passive"))
      (node (ref "Q6") (pin "6") (pinfunction "D_6") (pintype "passive"))
      (node (ref "Q6") (pin "7") (pinfunction "D_7") (pintype "passive"))
      (node (ref "Q6") (pin "8") (pinfunction "D_8") (pintype "passive"))
      (node (ref "R10") (pin "1") (pinfunction "1_1") (pintype "passive"))
      (node (ref "U3") (pin "6") (pinfunction "VS_6") (pintype "power_in"))
      (node (ref "X2") (pin "3") (pinfunction "3_3") (pintype "passive"))
    )
    (net (code "67") (name "W_BLDC-2CH") (class "Default")
      (node (ref "C13") (pin "2") (pinfunction "2_2") (pintype "passive"))
      (node (ref "Q11") (pin "1") (pinfunction "S_1") (pintype "passive"))
      (node (ref "Q11") (pin "2") (pinfunction "S_2") (pintype "passive"))
      (node (ref "Q11") (pin "3") (pinfunction "S_3") (pintype "passive"))
      (node (ref "Q12") (pin "5") (pinfunction "D_5") (pintype "passive"))
      (node (ref "Q12") (pin "6") (pinfunction "D_6") (pintype "passive"))
      (node (ref "Q12") (pin "7") (pinfunction "D_7") (pintype "passive"))
      (node (ref "Q12") (pin "8") (pinfunction "D_8") (pintype "passive"))
      (node (ref "R24") (pin "1") (pinfunction "1_1") (pintype "passive"))
      (node (ref "U7") (pin "6") (pinfunction "VS_6") (pintype "power_in"))
      (node (ref "X3") (pin "3") (pinfunction "3_3") (pintype "passive"))
    )
    (net (code "68") (name "W_IN-1CH") (class "Default")
      (node (ref "IC1") (pin "10") (pinfunction "PD6(AIN0)_10") (pintype "bidirectional"))
      (node (ref "U3") (pin "2") (pinfunction "IN_2") (pintype "input"))
    )
    (net (code "69") (name "W_IN-2CH") (class "Default")
      (node (ref "IC2") (pin "10") (pinfunction "PD6(AIN0)_10") (pintype "bidirectional"))
      (node (ref "U7") (pin "2") (pinfunction "IN_2") (pintype "input"))
    )
    (net (code "70") (name "W_SD-1CH") (class "Default")
      (node (ref "IC1") (pin "12") (pinfunction "PB0(ICP)_12") (pintype "bidirectional"))
      (node (ref "U3") (pin "3") (pinfunction "~{SD}_3") (pintype "input"))
    )
    (net (code "71") (name "W_SD-2CH") (class "Default")
      (node (ref "IC2") (pin "12") (pinfunction "PB0(ICP)_12") (pintype "bidirectional"))
      (node (ref "U7") (pin "3") (pinfunction "~{SD}_3") (pintype "input"))
    )
    (net (code "72") (name "unconnected-(IC1-ADC6-Pad19)") (class "Default")
      (node (ref "IC1") (pin "19") (pinfunction "ADC6_19") (pintype "bidirectional"))
    )
    (net (code "73") (name "unconnected-(IC1-ADC7-Pad22)") (class "Default")
      (node (ref "IC1") (pin "22") (pinfunction "ADC7_22") (pintype "bidirectional"))
    )
    (net (code "74") (name "unconnected-(IC1-PB1(OC1A)-Pad13)") (class "Default")
      (node (ref "IC1") (pin "13") (pinfunction "PB1(OC1A)_13") (pintype "bidirectional"))
    )
    (net (code "75") (name "unconnected-(IC1-PC4(ADC4{slash}SDA)-Pad27)") (class "Default")
      (node (ref "IC1") (pin "27") (pinfunction "PC4(ADC4/SDA)_27") (pintype "bidirectional"))
    )
    (net (code "76") (name "unconnected-(IC1-PC5(ADC5{slash}SCL)-Pad28)") (class "Default")
      (node (ref "IC1") (pin "28") (pinfunction "PC5(ADC5/SCL)_28") (pintype "bidirectional"))
    )
    (net (code "77") (name "unconnected-(IC1-PD1(TXD)-Pad31)") (class "Default")
      (node (ref "IC1") (pin "31") (pinfunction "PD1(TXD)_31") (pintype "bidirectional"))
    )
    (net (code "78") (name "unconnected-(IC1-PD2(INT0)-Pad32)") (class "Default")
      (node (ref "IC1") (pin "32") (pinfunction "PD2(INT0)_32") (pintype "bidirectional"))
    )
    (net (code "79") (name "unconnected-(IC2-ADC6-Pad19)") (class "Default")
      (node (ref "IC2") (pin "19") (pinfunction "ADC6_19") (pintype "bidirectional"))
    )
    (net (code "80") (name "unconnected-(IC2-ADC7-Pad22)") (class "Default")
      (node (ref "IC2") (pin "22") (pinfunction "ADC7_22") (pintype "bidirectional"))
    )
    (net (code "81") (name "unconnected-(IC2-PB1(OC1A)-Pad13)") (class "Default")
      (node (ref "IC2") (pin "13") (pinfunction "PB1(OC1A)_13") (pintype "bidirectional"))
    )
    (net (code "82") (name "unconnected-(IC2-PC4(ADC4{slash}SDA)-Pad27)") (class "Default")
      (node (ref "IC2") (pin "27") (pinfunction "PC4(ADC4/SDA)_27") (pintype "bidirectional"))
    )
    (net (code "83") (name "unconnected-(IC2-PC5(ADC5{slash}SCL)-Pad28)") (class "Default")
      (node (ref "IC2") (pin "28") (pinfunction "PC5(ADC5/SCL)_28") (pintype "bidirectional"))
    )
    (net (code "84") (name "unconnected-(IC2-PD1(TXD)-Pad31)") (class "Default")
      (node (ref "IC2") (pin "31") (pinfunction "PD1(TXD)_31") (pintype "bidirectional"))
    )
    (net (code "85") (name "unconnected-(IC2-PD2(INT0)-Pad32)") (class "Default")
      (node (ref "IC2") (pin "32") (pinfunction "PD2(INT0)_32") (pintype "bidirectional"))
    )
    (net (code "86") (name "unconnected-(JP1-Pad8)") (class "Default")
      (node (ref "JP1") (pin "8") (pinfunction "8_8") (pintype "passive"))
    )
    (net (code "87") (name "~{RESET1}") (class "Default")
      (node (ref "IC1") (pin "29") (pinfunction "PC6(/RESET)_29") (pintype "bidirectional"))
      (node (ref "JP1") (pin "5") (pinfunction "5_5") (pintype "passive"))
      (node (ref "R14") (pin "2") (pinfunction "2_2") (pintype "passive"))
    )
    (net (code "88") (name "~{RESET2}") (class "Default")
      (node (ref "IC2") (pin "29") (pinfunction "PC6(/RESET)_29") (pintype "bidirectional"))
      (node (ref "JP1") (pin "7") (pinfunction "7_7") (pintype "passive"))
      (node (ref "R27") (pin "2") (pinfunction "2_2") (pintype "passive"))
    )
  )
)
